# Sensor.net
KiCad netlist of a schematic drawn in Altium Designer
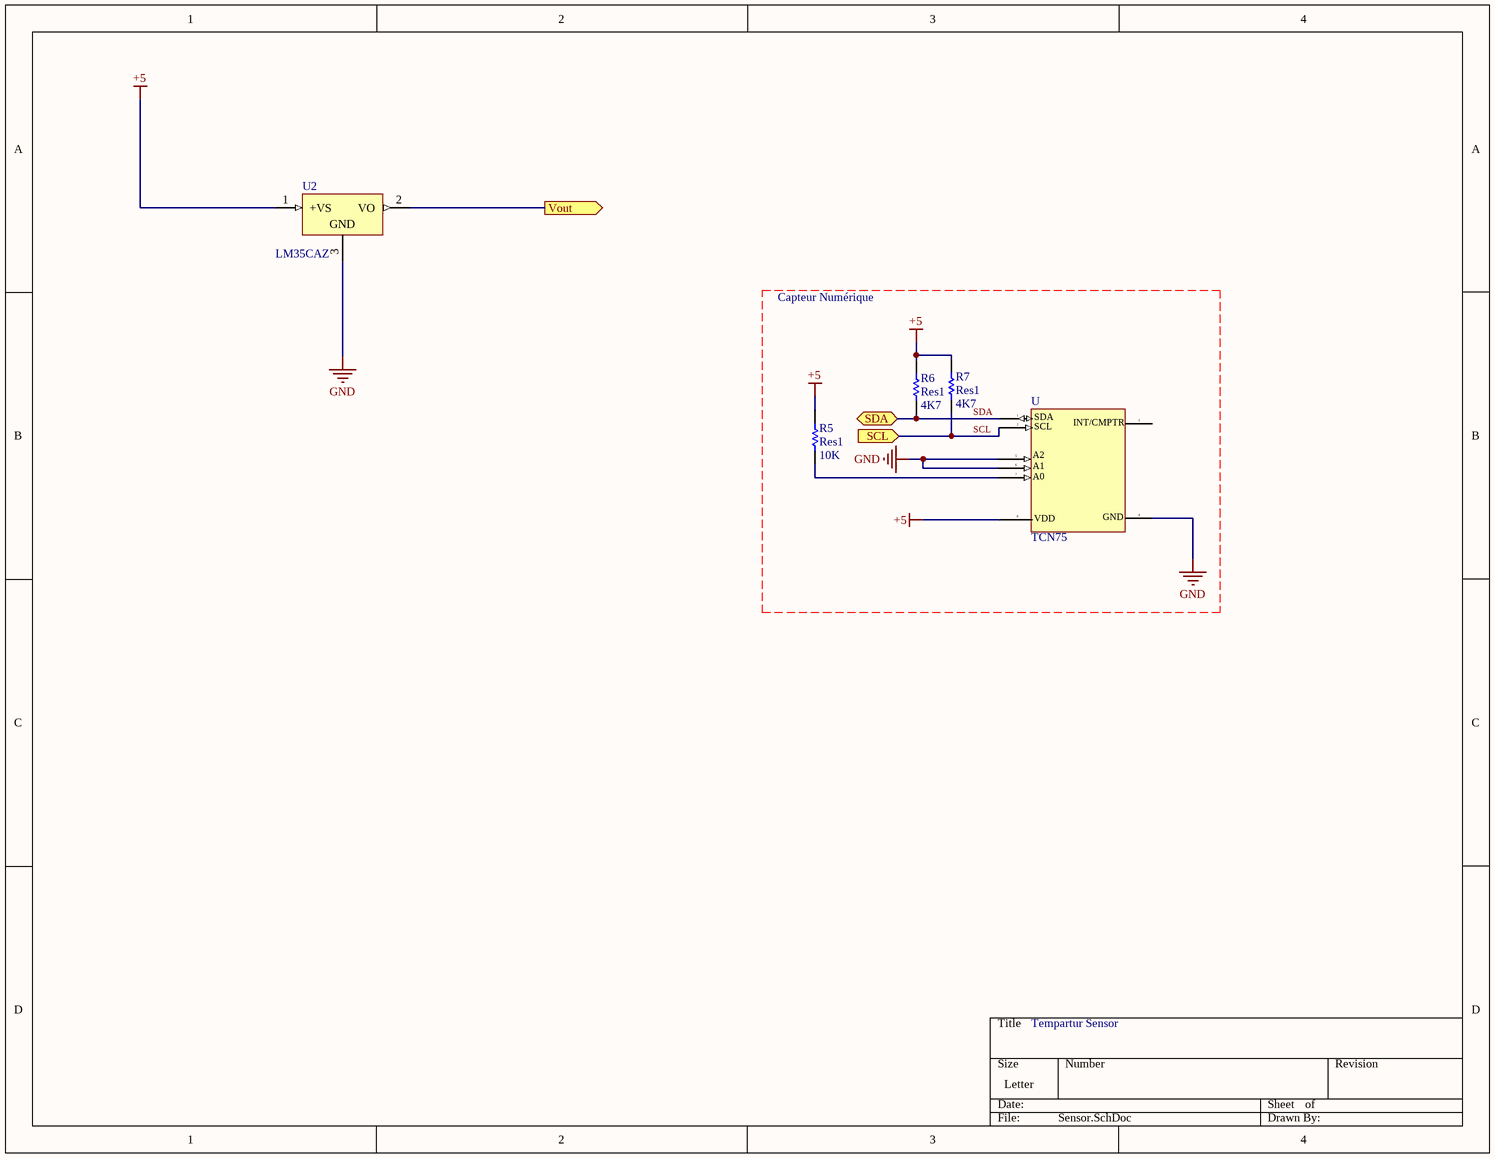
[diagram p0: Sensor.SchDoc]

(export (version "E")
  (design (tool "Eeschema 10.0.6"))
  (components
    (comp (ref "R5")
      (value "Res1")
      (footprint "AXIAL-0.3")
      (description "Resistor")
      (fields (field (name "ALTIUM_VALUE") "10K") (field (name "PUBLISHER") "Altium Limited"))
      (libsource (lib "Miscellaneous Devices") (part "Res1"))
    )
    (comp (ref "R6")
      (value "Res1")
      (footprint "AXIAL-0.3")
      (description "Resistor")
      (fields (field (name "ALTIUM_VALUE") "4K7") (field (name "PUBLISHER") "Altium Limited"))
      (libsource (lib "Miscellaneous Devices") (part "Res1"))
    )
    (comp (ref "R7")
      (value "Res1")
      (footprint "AXIAL-0.3")
      (description "Resistor")
      (fields (field (name "ALTIUM_VALUE") "4K7") (field (name "PUBLISHER") "Altium Limited"))
      (libsource (lib "Miscellaneous Devices") (part "Res1"))
    )
    (comp (ref "U") (value "TCN75") (libsource (lib "TP3") (part "TCN75")))
    (comp (ref "U2")
      (value "LM35CAZ")
      (footprint "Z03A")
      (description "Precision Centigrade Temperature Sensor, 3-pin TO-92")
      (fields
        (field (name "MANUFACTURER") "National Semiconductor")
        (field (name "PUBLISHER") "Altium Limited")
      )
      (libsource (lib "NSC Temperature Sensor") (part "LM35CAZ"))
    )
  )
  (nets
    (net (code "1") (name "+5") (class "Default")
      (node (ref "R5") (pin "2") (pinfunction "2_2") (pintype "passive"))
      (node (ref "R6") (pin "2") (pinfunction "2_2") (pintype "passive"))
      (node (ref "R7") (pin "2") (pinfunction "2_2") (pintype "passive"))
      (node (ref "U") (pin "8") (pintype "passive"))
      (node (ref "U2") (pin "1") (pinfunction "+VS_1") (pintype "input"))
    )
    (net (code "2") (name "/SCL") (class "Default")
      (node (ref "R7") (pin "1") (pinfunction "1_1") (pintype "passive"))
      (node (ref "U") (pin "2") (pintype "input"))
    )
    (net (code "3") (name "/SDA") (class "Default")
      (node (ref "R6") (pin "1") (pinfunction "1_1") (pintype "passive"))
      (node (ref "U") (pin "1") (pintype "bidirectional"))
    )
    (net (code "4") (name "/Vout") (class "Default")
      (node (ref "U2") (pin "2") (pinfunction "VO_2") (pintype "output"))
    )
    (net (code "5") (name "GND") (class "Default")
      (node (ref "U") (pin "4") (pintype "passive"))
      (node (ref "U") (pin "5") (pintype "input"))
      (node (ref "U") (pin "6") (pintype "input"))
      (node (ref "U2") (pin "3") (pinfunction "GND_3") (pintype "power_in"))
    )
    (net (code "6") (name "Net-(R5-Pad1)") (class "Default")
      (node (ref "R5") (pin "1") (pinfunction "1_1") (pintype "passive"))
      (node (ref "U") (pin "7") (pintype "input"))
    )
    (net (code "7") (name "unconnected-(U-Pad3)") (class "Default")
      (node (ref "U") (pin "3") (pintype "passive"))
    )
  )
)
